# power.net
KiCad netlist of a schematic drawn in Altium Designer
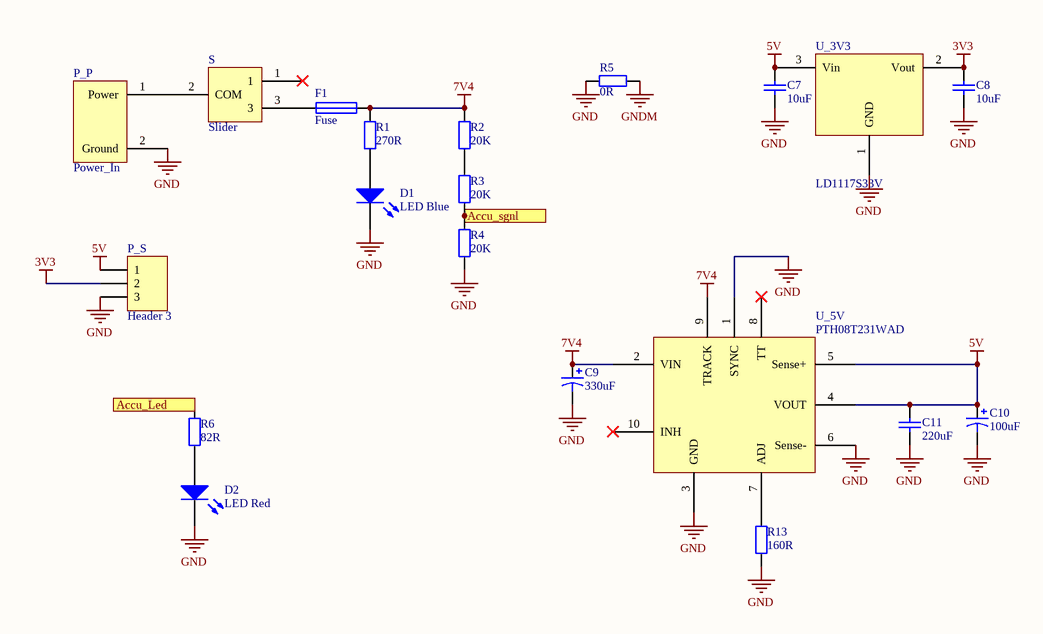
[diagram p0: power.SchDoc]

(export (version "E")
  (design (tool "Eeschema 10.0.6"))
  (components
    (comp (ref "C7")
      (value "10uF")
      (footprint "FP_0805_CAP_085")
      (description "Capacitor")
      (fields (field (name "TOLERANCE") "10%") (field (name "VOLTAGE") "16V"))
      (libsource (lib "hallglib") (part "CAP 10uF"))
    )
    (comp (ref "C8")
      (value "10uF")
      (footprint "FP_0805_CAP_085")
      (description "Capacitor")
      (fields (field (name "TOLERANCE") "10%") (field (name "VOLTAGE") "16V"))
      (libsource (lib "hallglib") (part "CAP 10uF"))
    )
    (comp (ref "C9")
      (value "330uF")
      (footprint "FP_7343")
      (description "Polarized Capacitor")
      (fields (field (name "VOLTAGE") "10V") (field (name "TOLERANCE") "20%"))
      (libsource (lib "hallglib") (part "CAP_ELECT"))
    )
    (comp (ref "C10")
      (value "100uF")
      (footprint "FP_3528")
      (description "Polarized Capacitor")
      (fields (field (name "VOLTAGE") "6.3V") (field (name "TOLERANCE") "10%"))
      (libsource (lib "hallglib") (part "CAP_ELECT"))
    )
    (comp (ref "C11")
      (value "220uF")
      (footprint "FP_1206_CAP_125")
      (description "Capacitor")
      (fields (field (name "TOLERANCE") "20%") (field (name "VOLTAGE") "6.3V"))
      (libsource (lib "hallglib") (part "CAP"))
    )
    (comp (ref "D1")
      (value "LED Blue")
      (footprint "FP_0805_LED_RED")
      (description "Blue LED")
      (libsource (lib "hallglib") (part "LED Blue"))
    )
    (comp (ref "D2")
      (value "LED Red")
      (footprint "FP_0805_LED_RED")
      (description "Red LED")
      (libsource (lib "hallglib") (part "LED Red"))
    )
    (comp (ref "F1") (value "Fuse") (footprint "MULTIFUSE") (libsource (lib "qlib") (part "Fuse")))
    (comp (ref "P_P") (value "Power_In") (footprint "SORK.3.81mm") (libsource (lib "qlib") (part "Power_In")))
    (comp (ref "P_S")
      (value "Header 3")
      (footprint "HDR1X3")
      (description "Header, 3-Pin")
      (fields (field (name "PUBLISHER") "Altium Limited"))
      (libsource (lib "Miscellaneous Connectors") (part "Header 3"))
    )
    (comp (ref "R1")
      (value "270R")
      (footprint "FP_0805_RES")
      (description "Resistor")
      (fields (field (name "TOLERANCE") "5%") (field (name "POWER") "125mW"))
      (libsource (lib "hallglib") (part "RES 270R"))
    )
    (comp (ref "R2")
      (value "20K")
      (footprint "FP_0805_RES")
      (description "Resistor")
      (fields (field (name "TOLERANCE") "1%") (field (name "POWER") "0.125W"))
      (libsource (lib "hallglib") (part "RES"))
    )
    (comp (ref "R3")
      (value "20K")
      (footprint "FP_0805_RES")
      (description "Resistor")
      (fields (field (name "TOLERANCE") "1%") (field (name "POWER") "0.125W"))
      (libsource (lib "hallglib") (part "RES"))
    )
    (comp (ref "R4")
      (value "20K")
      (footprint "FP_0805_RES")
      (description "Resistor")
      (fields (field (name "TOLERANCE") "1%") (field (name "POWER") "0.125W"))
      (libsource (lib "hallglib") (part "RES"))
    )
    (comp (ref "R5")
      (value "0R")
      (footprint "FP_0805_RES")
      (description "Resistor")
      (fields (field (name "POWER") "0.125W"))
      (libsource (lib "") (part "RES_1"))
    )
    (comp (ref "R6")
      (value "82R")
      (footprint "FP_0805_RES")
      (description "Resistor")
      (fields (field (name "TOLERANCE") "5%") (field (name "POWER") "125mW"))
      (libsource (lib "hallglib") (part "RES 82R"))
    )
    (comp (ref "R13")
      (value "160R")
      (footprint "FP_0805_RES")
      (description "Resistor")
      (fields (field (name "TOLERANCE") "1%") (field (name "POWER") "0.125W"))
      (libsource (lib "hallglib") (part "RES"))
    )
    (comp (ref "S") (value "Slider") (footprint "Slide") (libsource (lib "qlib") (part "Slider")))
    (comp (ref "U_3V3")
      (value "LD1117S33V")
      (footprint "FP_SOT223")
      (libsource (lib "qlib") (part "LD1117S33V"))
    )
    (comp (ref "U_5V")
      (value "PTH08T231WAD")
      (footprint "5V SUPPLY")
      (libsource (lib "qlib") (part "5V_SUPPLY"))
    )
  )
  (nets
    (net (code "1") (name "/Accu_Led") (class "Default")
      (node (ref "R6") (pin "2") (pinfunction "2_2") (pintype "passive"))
    )
    (net (code "2") (name "/Accu_sgnl") (class "Default")
      (node (ref "R3") (pin "1") (pinfunction "1_1") (pintype "passive"))
      (node (ref "R4") (pin "2") (pinfunction "2_2") (pintype "passive"))
    )
    (net (code "3") (name "3V3") (class "Default")
      (node (ref "C8") (pin "2") (pinfunction "2_2") (pintype "passive"))
      (node (ref "P_S") (pin "2") (pinfunction "2_2") (pintype "passive"))
      (node (ref "U_3V3") (pin "2") (pinfunction "Vout_2") (pintype "passive"))
    )
    (net (code "4") (name "5V") (class "Default")
      (node (ref "C10") (pin "P") (pinfunction "P_P") (pintype "passive"))
      (node (ref "C11") (pin "2") (pinfunction "2_2") (pintype "passive"))
      (node (ref "C7") (pin "2") (pinfunction "2_2") (pintype "passive"))
      (node (ref "P_S") (pin "1") (pinfunction "1_1") (pintype "passive"))
      (node (ref "U_3V3") (pin "3") (pinfunction "Vin_3") (pintype "passive"))
      (node (ref "U_5V") (pin "4") (pinfunction "VOUT_4") (pintype "passive"))
      (node (ref "U_5V") (pin "5") (pinfunction "Sense+_5") (pintype "passive"))
    )
    (net (code "5") (name "7V4") (class "Default")
      (node (ref "C9") (pin "P") (pinfunction "P_P") (pintype "passive"))
      (node (ref "F1") (pin "2") (pinfunction "2_2") (pintype "passive"))
      (node (ref "R1") (pin "2") (pinfunction "2_2") (pintype "passive"))
      (node (ref "R2") (pin "2") (pinfunction "2_2") (pintype "passive"))
      (node (ref "U_5V") (pin "2") (pinfunction "VIN_2") (pintype "passive"))
      (node (ref "U_5V") (pin "9") (pinfunction "TRACK_9") (pintype "passive"))
    )
    (net (code "6") (name "GND") (class "Default")
      (node (ref "C10") (pin "N") (pinfunction "N_N") (pintype "passive"))
      (node (ref "C11") (pin "1") (pinfunction "1_1") (pintype "passive"))
      (node (ref "C7") (pin "1") (pinfunction "1_1") (pintype "passive"))
      (node (ref "C8") (pin "1") (pinfunction "1_1") (pintype "passive"))
      (node (ref "C9") (pin "N") (pinfunction "N_N") (pintype "passive"))
      (node (ref "D1") (pin "2") (pinfunction "K_2") (pintype "passive"))
      (node (ref "D2") (pin "2") (pinfunction "K_2") (pintype "passive"))
      (node (ref "P_P") (pin "2") (pinfunction "Ground_2") (pintype "passive"))
      (node (ref "P_S") (pin "3") (pinfunction "3_3") (pintype "passive"))
      (node (ref "R13") (pin "1") (pinfunction "1_1") (pintype "passive"))
      (node (ref "R4") (pin "1") (pinfunction "1_1") (pintype "passive"))
      (node (ref "R5") (pin "1") (pinfunction "1_1") (pintype "passive"))
      (node (ref "U_3V3") (pin "1") (pinfunction "GND_1") (pintype "passive"))
      (node (ref "U_5V") (pin "1") (pinfunction "SYNC_1") (pintype "passive"))
      (node (ref "U_5V") (pin "3") (pinfunction "GND_3") (pintype "passive"))
      (node (ref "U_5V") (pin "6") (pinfunction "Sense-_6") (pintype "passive"))
    )
    (net (code "7") (name "GNDM") (class "Default")
      (node (ref "R5") (pin "2") (pinfunction "2_2") (pintype "passive"))
    )
    (net (code "8") (name "Net-(D1-A)") (class "Default")
      (node (ref "D1") (pin "1") (pinfunction "A_1") (pintype "passive"))
      (node (ref "R1") (pin "1") (pinfunction "1_1") (pintype "passive"))
    )
    (net (code "9") (name "Net-(D2-A)") (class "Default")
      (node (ref "D2") (pin "1") (pinfunction "A_1") (pintype "passive"))
      (node (ref "R6") (pin "1") (pinfunction "1_1") (pintype "passive"))
    )
    (net (code "10") (name "Net-(F1-Pad1)") (class "Default")
      (node (ref "F1") (pin "1") (pinfunction "1_1") (pintype "passive"))
      (node (ref "S") (pin "3") (pinfunction "3_3") (pintype "passive"))
    )
    (net (code "11") (name "Net-(P_P-Power)") (class "Default")
      (node (ref "P_P") (pin "1") (pinfunction "Power_1") (pintype "passive"))
      (node (ref "S") (pin "2") (pinfunction "COM_2") (pintype "passive"))
    )
    (net (code "12") (name "Net-(R2-Pad1)") (class "Default")
      (node (ref "R2") (pin "1") (pinfunction "1_1") (pintype "passive"))
      (node (ref "R3") (pin "2") (pinfunction "2_2") (pintype "passive"))
    )
    (net (code "13") (name "Net-(U_5V-ADJ)") (class "Default")
      (node (ref "R13") (pin "2") (pinfunction "2_2") (pintype "passive"))
      (node (ref "U_5V") (pin "7") (pinfunction "ADJ_7") (pintype "passive"))
    )
    (net (code "14") (name "unconnected-(S-Pad1)") (class "Default")
      (node (ref "S") (pin "1") (pinfunction "1_1") (pintype "passive+no_connect"))
    )
    (net (code "15") (name "unconnected-(U_5V-INH-Pad10)") (class "Default")
      (node (ref "U_5V") (pin "10") (pinfunction "INH_10") (pintype "passive+no_connect"))
    )
    (net (code "16") (name "unconnected-(U_5V-TT-Pad8)") (class "Default")
      (node (ref "U_5V") (pin "8") (pinfunction "TT_8") (pintype "passive+no_connect"))
    )
  )
)
